# Sheet1.net
KiCad netlist of a schematic drawn in Altium Designer
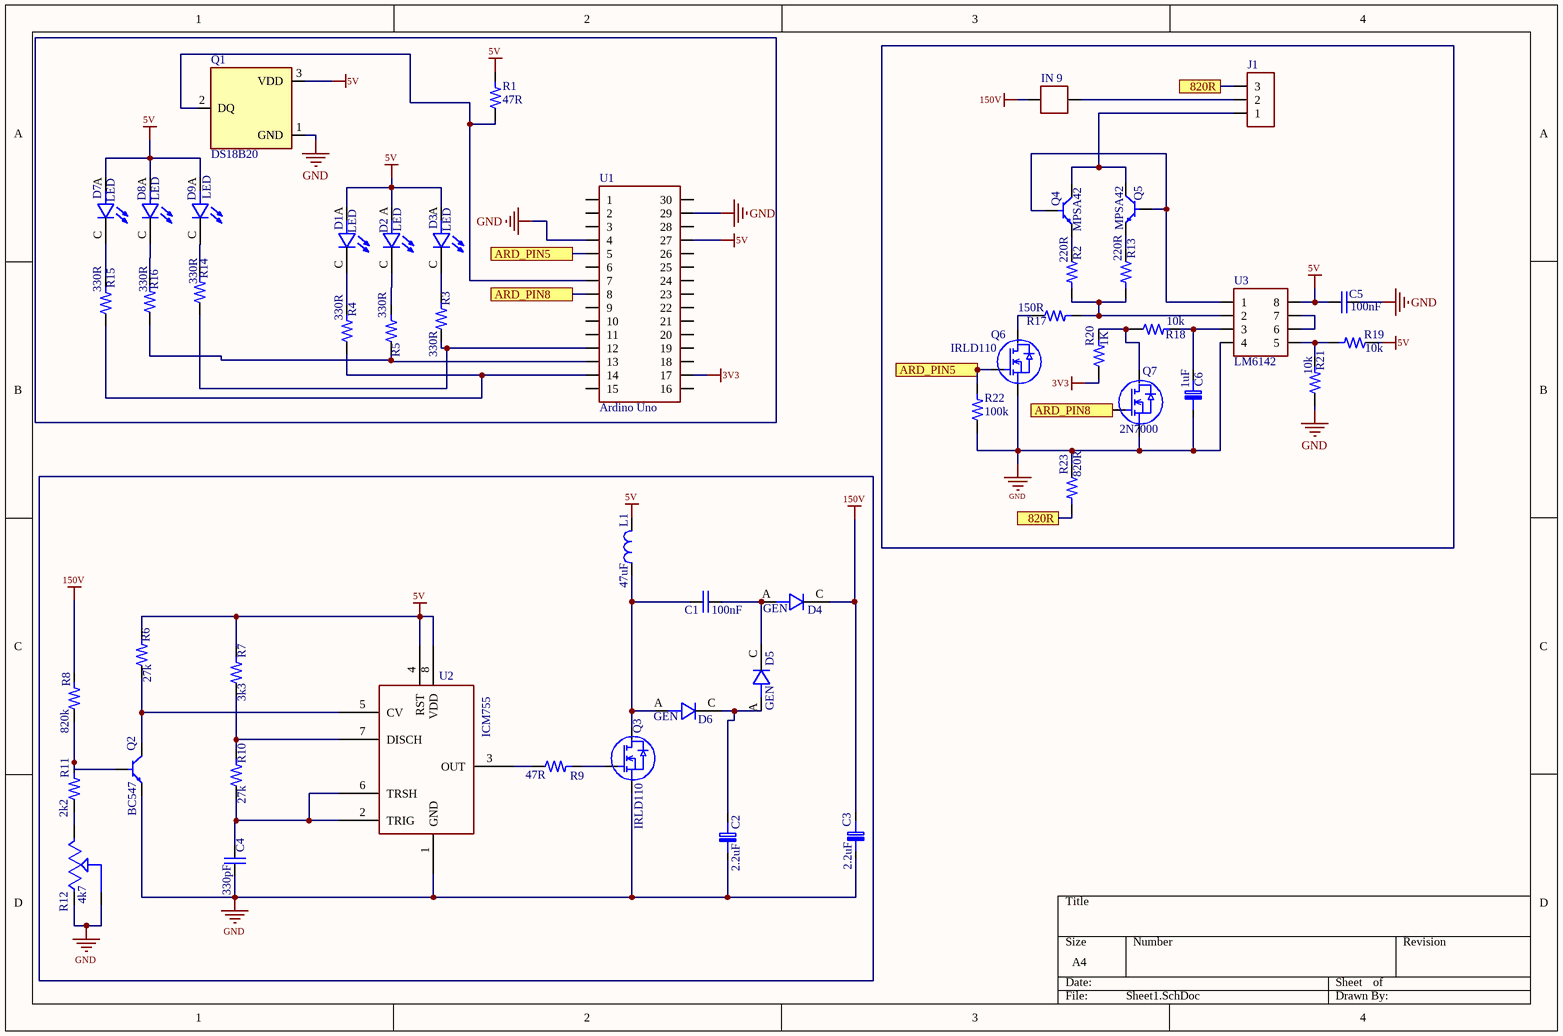
[diagram p0: Sheet1.SchDoc]

(export (version "E")
  (design (tool "Eeschema 10.0.6"))
  (components
    (comp (ref "C1") (value "100nF") (footprint "CAP 0805") (libsource (lib "Schlib1") (part "CAP 100nF")))
    (comp (ref "C2") (value "2.2uF") (footprint "CAP 1005") (libsource (lib "Schlib1") (part "CAP 2.2uF")))
    (comp (ref "C3") (value "2.2uF") (footprint "CAP 1005") (libsource (lib "Schlib1") (part "CAP 2.2uF")))
    (comp (ref "C4") (value "330pF") (footprint "CAP 0805") (libsource (lib "Schlib1") (part "CAP 330pF")))
    (comp (ref "C5") (value "100nF") (footprint "CAP 0805") (libsource (lib "Schlib1") (part "CAP 100nF")))
    (comp (ref "C6") (value "1uF") (footprint "CAP 1005") (libsource (lib "Schlib1") (part "CAP 1uF")))
    (comp (ref "D1") (value "LED") (footprint "LED") (libsource (lib "Schlib1") (part "LED")))
    (comp (ref "D2") (value "LED") (footprint "LED") (libsource (lib "Schlib1") (part "LED")))
    (comp (ref "D3") (value "LED") (footprint "LED") (libsource (lib "Schlib1") (part "LED")))
    (comp (ref "D4") (value "GEN") (footprint "MUR160G") (libsource (lib "Schlib1") (part "Diode")))
    (comp (ref "D5") (value "GEN") (footprint "MUR160G") (libsource (lib "Schlib1") (part "Diode")))
    (comp (ref "D6") (value "GEN") (footprint "MUR160G") (libsource (lib "Schlib1") (part "Diode")))
    (comp (ref "D7") (value "LED") (footprint "LED") (libsource (lib "Schlib1") (part "LED")))
    (comp (ref "D8") (value "LED") (footprint "LED") (libsource (lib "Schlib1") (part "LED")))
    (comp (ref "D9") (value "LED") (footprint "LED") (libsource (lib "Schlib1") (part "LED")))
    (comp (ref "IN 9")
      (value "IN_9 CONNECTOR")
      (footprint "IN 9")
      (libsource (lib "Schlib1") (part "IN_9 CONNECTOR"))
    )
    (comp (ref "J1")
      (value "3 PIN CONNECTOR")
      (footprint "3 PIN CONNECTOR")
      (libsource (lib "Schlib1") (part "3 PIN CONNECTOR"))
    )
    (comp (ref "L1")
      (value "47uF")
      (footprint "INDUCTOR 47uH")
      (libsource (lib "Schlib1") (part "INDUCTOR 47uH"))
    )
    (comp (ref "Q1") (value "DS18B20") (footprint "DS18B20") (libsource (lib "Schlib1") (part "DS18B20")))
    (comp (ref "Q2") (value "BC547") (footprint "BC547") (libsource (lib "Schlib1") (part "BC547")))
    (comp (ref "Q3") (value "IRLD110") (footprint "IRLD110") (libsource (lib "Schlib1") (part "IRLD110")))
    (comp (ref "Q4") (value "MPSA42") (footprint "MPSA42") (libsource (lib "Schlib1") (part "MPSA42")))
    (comp (ref "Q5") (value "MPSA42") (footprint "MPSA42") (libsource (lib "Schlib1") (part "MPSA42")))
    (comp (ref "Q6") (value "IRLD110") (footprint "IRLD110") (libsource (lib "Schlib1") (part "IRLD110")))
    (comp (ref "Q7") (value "2N7000") (footprint "2N7000") (libsource (lib "Schlib1") (part "2N7000")))
    (comp (ref "R1") (value "47R") (footprint "RES 1206") (libsource (lib "Schlib1") (part "RES 47R")))
    (comp (ref "R2") (value "220R") (footprint "RES 1206") (libsource (lib "Schlib1") (part "RES 220R")))
    (comp (ref "R3") (value "330R") (footprint "RES 1206") (libsource (lib "Schlib1") (part "RES 330")))
    (comp (ref "R4") (value "330R") (footprint "RES 1206") (libsource (lib "Schlib1") (part "RES 330")))
    (comp (ref "R5") (value "330R") (footprint "RES 1206") (libsource (lib "Schlib1") (part "RES 330")))
    (comp (ref "R6") (value "27k") (footprint "RES 1206") (libsource (lib "Schlib1") (part "RES 27K")))
    (comp (ref "R7") (value "3k3") (footprint "RES 1206") (libsource (lib "Schlib1") (part "RES 3K3")))
    (comp (ref "R8") (value "820k") (footprint "RES 1206") (libsource (lib "Schlib1") (part "RES 820K")))
    (comp (ref "R9") (value "47R") (footprint "RES 1206") (libsource (lib "Schlib1") (part "RES 47R")))
    (comp (ref "R10") (value "27k") (footprint "RES 1206") (libsource (lib "Schlib1") (part "RES 27K")))
    (comp (ref "R11") (value "2k2") (footprint "RES 1206") (libsource (lib "Schlib1") (part "RES 2K2")))
    (comp (ref "R12")
      (value "4k7")
      (footprint "POTENTIOMETER")
      (libsource (lib "Schlib1") (part "POTENTIOMETER"))
    )
    (comp (ref "R13") (value "220R") (footprint "RES 1206") (libsource (lib "Schlib1") (part "RES 220R")))
    (comp (ref "R14") (value "330R") (footprint "RES 1206") (libsource (lib "Schlib1") (part "RES 330")))
    (comp (ref "R15") (value "330R") (footprint "RES 1206") (libsource (lib "Schlib1") (part "RES 330")))
    (comp (ref "R16") (value "330R") (footprint "RES 1206") (libsource (lib "Schlib1") (part "RES 330")))
    (comp (ref "R17") (value "150R") (footprint "RES 1206") (libsource (lib "Schlib1") (part "RES 150R")))
    (comp (ref "R18") (value "10k") (footprint "RES 1206") (libsource (lib "Schlib1") (part "RES 10K")))
    (comp (ref "R19") (value "10k") (footprint "RES 1206") (libsource (lib "Schlib1") (part "RES 10K")))
    (comp (ref "R20") (value "1K") (footprint "RES 1206") (libsource (lib "Schlib1") (part "RES 1K")))
    (comp (ref "R21") (value "10k") (footprint "RES 1206") (libsource (lib "Schlib1") (part "RES 10K")))
    (comp (ref "R22") (value "100k") (footprint "RES 1206") (libsource (lib "Schlib1") (part "RES 100K")))
    (comp (ref "R23") (value "820R") (footprint "RES 1206") (libsource (lib "Schlib1") (part "RES 820R")))
    (comp (ref "U1")
      (value "Ardino Uno")
      (footprint "ARDUINO NANO")
      (libsource (lib "Schlib1") (part "ARDUINO NANO"))
    )
    (comp (ref "U2") (value "ICM755") (footprint "ICM7555") (libsource (lib "Schlib1") (part "ICM755")))
    (comp (ref "U3") (value "LM6142") (footprint "LM6142") (libsource (lib "Schlib1") (part "LM6142")))
  )
  (nets
    (net (code "1") (name "/820R") (class "Default")
      (node (ref "J1") (pin "3") (pinfunction "3_3") (pintype "passive"))
      (node (ref "R23") (pin "2") (pinfunction "2_2") (pintype "passive"))
    )
    (net (code "2") (name "/ARD_PIN5") (class "Default")
      (node (ref "Q6") (pin "G") (pinfunction "G_G") (pintype "passive"))
      (node (ref "R22") (pin "2") (pinfunction "2_2") (pintype "passive"))
      (node (ref "U1") (pin "5") (pinfunction "5_5") (pintype "passive"))
    )
    (net (code "3") (name "/ARD_PIN8") (class "Default")
      (node (ref "Q7") (pin "1") (pinfunction "1_1") (pintype "passive"))
      (node (ref "U1") (pin "8") (pinfunction "8_8") (pintype "passive"))
    )
    (net (code "4") (name "3V3") (class "Default")
      (node (ref "R20") (pin "1") (pinfunction "1_1") (pintype "passive"))
      (node (ref "U1") (pin "17") (pinfunction "17_17") (pintype "passive"))
    )
    (net (code "5") (name "5V") (class "Default")
      (node (ref "C5") (pin "1") (pinfunction "1_1") (pintype "passive"))
      (node (ref "D1") (pin "A") (pinfunction "A_A") (pintype "passive"))
      (node (ref "D2") (pin "A") (pinfunction "A_A") (pintype "passive"))
      (node (ref "D3") (pin "A") (pinfunction "A_A") (pintype "passive"))
      (node (ref "D7") (pin "A") (pinfunction "A_A") (pintype "passive"))
      (node (ref "D8") (pin "A") (pinfunction "A_A") (pintype "passive"))
      (node (ref "D9") (pin "A") (pinfunction "A_A") (pintype "passive"))
      (node (ref "L1") (pin "2") (pinfunction "2_2") (pintype "passive"))
      (node (ref "Q1") (pin "3") (pinfunction "VDD_3") (pintype "power_in"))
      (node (ref "R1") (pin "2") (pinfunction "2_2") (pintype "passive"))
      (node (ref "R19") (pin "1") (pinfunction "1_1") (pintype "passive"))
      (node (ref "R6") (pin "2") (pinfunction "2_2") (pintype "passive"))
      (node (ref "R7") (pin "2") (pinfunction "2_2") (pintype "passive"))
      (node (ref "U1") (pin "27") (pinfunction "27_27") (pintype "passive"))
      (node (ref "U2") (pin "4") (pinfunction "RST_4") (pintype "passive"))
      (node (ref "U2") (pin "8") (pinfunction "VDD_8") (pintype "passive"))
      (node (ref "U3") (pin "8") (pinfunction "8_8") (pintype "passive"))
    )
    (net (code "6") (name "150V") (class "Default")
      (node (ref "C3") (pin "1") (pinfunction "1_1") (pintype "passive"))
      (node (ref "D4") (pin "C") (pinfunction "C_C") (pintype "passive"))
      (node (ref "IN 9") (pin "1") (pinfunction "1_1") (pintype "passive"))
      (node (ref "R8") (pin "2") (pinfunction "2_2") (pintype "passive"))
    )
    (net (code "7") (name "GND") (class "Default")
      (node (ref "C2") (pin "2") (pinfunction "2_2") (pintype "passive"))
      (node (ref "C3") (pin "2") (pinfunction "2_2") (pintype "passive"))
      (node (ref "C4") (pin "1") (pinfunction "1_1") (pintype "passive"))
      (node (ref "C5") (pin "2") (pinfunction "2_2") (pintype "passive"))
      (node (ref "C6") (pin "2") (pinfunction "2_2") (pintype "passive"))
      (node (ref "Q1") (pin "1") (pinfunction "GND_1") (pintype "power_in"))
      (node (ref "Q2") (pin "3") (pinfunction "3_3") (pintype "passive"))
      (node (ref "Q3") (pin "S") (pinfunction "S_S") (pintype "passive"))
      (node (ref "Q6") (pin "S") (pinfunction "S_S") (pintype "passive"))
      (node (ref "Q7") (pin "2") (pinfunction "2_2") (pintype "passive"))
      (node (ref "R12") (pin "1") (pinfunction "1_1") (pintype "passive"))
      (node (ref "R12") (pin "2") (pinfunction "2_2") (pintype "passive"))
      (node (ref "R21") (pin "1") (pinfunction "1_1") (pintype "passive"))
      (node (ref "R22") (pin "1") (pinfunction "1_1") (pintype "passive"))
      (node (ref "R23") (pin "1") (pinfunction "1_1") (pintype "passive"))
      (node (ref "U1") (pin "29") (pinfunction "29_29") (pintype "passive"))
      (node (ref "U1") (pin "4") (pinfunction "4_4") (pintype "passive"))
      (node (ref "U2") (pin "1") (pinfunction "GND_1") (pintype "passive"))
      (node (ref "U3") (pin "4") (pinfunction "4_4") (pintype "passive"))
    )
    (net (code "8") (name "Net-(C1-Pad1)") (class "Default")
      (node (ref "C1") (pin "1") (pinfunction "1_1") (pintype "passive"))
      (node (ref "D6") (pin "A") (pinfunction "A_A") (pintype "passive"))
      (node (ref "L1") (pin "1") (pinfunction "1_1") (pintype "passive"))
      (node (ref "Q3") (pin "D") (pinfunction "D_D") (pintype "passive"))
    )
    (net (code "9") (name "Net-(C1-Pad2)") (class "Default")
      (node (ref "C1") (pin "2") (pinfunction "2_2") (pintype "passive"))
      (node (ref "D4") (pin "A") (pinfunction "A_A") (pintype "passive"))
      (node (ref "D5") (pin "C") (pinfunction "C_C") (pintype "passive"))
    )
    (net (code "10") (name "Net-(C2-Pad1)") (class "Default")
      (node (ref "C2") (pin "1") (pinfunction "1_1") (pintype "passive"))
      (node (ref "D5") (pin "A") (pinfunction "A_A") (pintype "passive"))
      (node (ref "D6") (pin "C") (pinfunction "C_C") (pintype "passive"))
    )
    (net (code "11") (name "Net-(C6-Pad1)") (class "Default")
      (node (ref "C6") (pin "1") (pinfunction "1_1") (pintype "passive"))
      (node (ref "R18") (pin "2") (pinfunction "2_2") (pintype "passive"))
      (node (ref "U3") (pin "3") (pinfunction "3_3") (pintype "passive"))
    )
    (net (code "12") (name "Net-(D1-PadC)") (class "Default")
      (node (ref "D1") (pin "C") (pinfunction "C_C") (pintype "passive"))
      (node (ref "R4") (pin "2") (pinfunction "2_2") (pintype "passive"))
    )
    (net (code "13") (name "Net-(D2-PadC)") (class "Default")
      (node (ref "D2") (pin "C") (pinfunction "C_C") (pintype "passive"))
      (node (ref "R5") (pin "2") (pinfunction "2_2") (pintype "passive"))
    )
    (net (code "14") (name "Net-(D3-PadC)") (class "Default")
      (node (ref "D3") (pin "C") (pinfunction "C_C") (pintype "passive"))
      (node (ref "R3") (pin "2") (pinfunction "2_2") (pintype "passive"))
    )
    (net (code "15") (name "Net-(D7-PadC)") (class "Default")
      (node (ref "D7") (pin "C") (pinfunction "C_C") (pintype "passive"))
      (node (ref "R15") (pin "2") (pinfunction "2_2") (pintype "passive"))
    )
    (net (code "16") (name "Net-(D8-PadC)") (class "Default")
      (node (ref "D8") (pin "C") (pinfunction "C_C") (pintype "passive"))
      (node (ref "R16") (pin "2") (pinfunction "2_2") (pintype "passive"))
    )
    (net (code "17") (name "Net-(D9-PadC)") (class "Default")
      (node (ref "D9") (pin "C") (pinfunction "C_C") (pintype "passive"))
      (node (ref "R14") (pin "2") (pinfunction "2_2") (pintype "passive"))
    )
    (net (code "18") (name "Net-(IN 9-Pad2)") (class "Default")
      (node (ref "IN 9") (pin "2") (pinfunction "2_2") (pintype "passive"))
      (node (ref "J1") (pin "2") (pinfunction "2_2") (pintype "passive"))
    )
    (net (code "19") (name "Net-(J1-Pad1)") (class "Default")
      (node (ref "J1") (pin "1") (pinfunction "1_1") (pintype "passive"))
      (node (ref "Q4") (pin "3") (pinfunction "3_3") (pintype "passive"))
      (node (ref "Q5") (pin "3") (pinfunction "3_3") (pintype "passive"))
    )
    (net (code "20") (name "Net-(Q1-DQ)") (class "Default")
      (node (ref "Q1") (pin "2") (pinfunction "DQ_2") (pintype "bidirectional"))
      (node (ref "R1") (pin "1") (pinfunction "1_1") (pintype "passive"))
      (node (ref "U1") (pin "7") (pinfunction "7_7") (pintype "passive"))
    )
    (net (code "21") (name "Net-(Q2-Pad2)") (class "Default")
      (node (ref "Q2") (pin "2") (pinfunction "2_2") (pintype "passive"))
      (node (ref "R11") (pin "2") (pinfunction "2_2") (pintype "passive"))
      (node (ref "R8") (pin "1") (pinfunction "1_1") (pintype "passive"))
    )
    (net (code "22") (name "Net-(Q3-PadG)") (class "Default")
      (node (ref "Q3") (pin "G") (pinfunction "G_G") (pintype "passive"))
      (node (ref "R9") (pin "2") (pinfunction "2_2") (pintype "passive"))
    )
    (net (code "23") (name "Net-(Q4-Pad1)") (class "Default")
      (node (ref "Q4") (pin "1") (pinfunction "1_1") (pintype "passive"))
      (node (ref "R2") (pin "1") (pinfunction "1_1") (pintype "passive"))
    )
    (net (code "24") (name "Net-(Q4-Pad2)") (class "Default")
      (node (ref "Q4") (pin "2") (pinfunction "2_2") (pintype "passive"))
      (node (ref "Q5") (pin "2") (pinfunction "2_2") (pintype "passive"))
      (node (ref "U3") (pin "1") (pinfunction "1_1") (pintype "passive"))
    )
    (net (code "25") (name "Net-(Q5-Pad1)") (class "Default")
      (node (ref "Q5") (pin "1") (pinfunction "1_1") (pintype "passive"))
      (node (ref "R13") (pin "1") (pinfunction "1_1") (pintype "passive"))
    )
    (net (code "26") (name "Net-(Q6-PadD)") (class "Default")
      (node (ref "Q6") (pin "D") (pinfunction "D_D") (pintype "passive"))
      (node (ref "R17") (pin "1") (pinfunction "1_1") (pintype "passive"))
    )
    (net (code "27") (name "Net-(Q7-Pad3)") (class "Default")
      (node (ref "Q7") (pin "3") (pinfunction "3_3") (pintype "passive"))
      (node (ref "R18") (pin "1") (pinfunction "1_1") (pintype "passive"))
      (node (ref "R20") (pin "2") (pinfunction "2_2") (pintype "passive"))
    )
    (net (code "28") (name "Net-(R11-Pad1)") (class "Default")
      (node (ref "R11") (pin "1") (pinfunction "1_1") (pintype "passive"))
      (node (ref "R12") (pin "3") (pinfunction "3_3") (pintype "passive"))
    )
    (net (code "29") (name "Net-(R13-Pad2)") (class "Default")
      (node (ref "R13") (pin "2") (pinfunction "2_2") (pintype "passive"))
      (node (ref "R17") (pin "2") (pinfunction "2_2") (pintype "passive"))
      (node (ref "R2") (pin "2") (pinfunction "2_2") (pintype "passive"))
      (node (ref "U3") (pin "2") (pinfunction "2_2") (pintype "passive"))
    )
    (net (code "30") (name "Net-(R14-Pad1)") (class "Default")
      (node (ref "R14") (pin "1") (pinfunction "1_1") (pintype "passive"))
      (node (ref "R3") (pin "1") (pinfunction "1_1") (pintype "passive"))
      (node (ref "U1") (pin "12") (pinfunction "12_12") (pintype "passive"))
    )
    (net (code "31") (name "Net-(R15-Pad1)") (class "Default")
      (node (ref "R15") (pin "1") (pinfunction "1_1") (pintype "passive"))
      (node (ref "R4") (pin "1") (pinfunction "1_1") (pintype "passive"))
      (node (ref "U1") (pin "14") (pinfunction "14_14") (pintype "passive"))
    )
    (net (code "32") (name "Net-(R16-Pad1)") (class "Default")
      (node (ref "R16") (pin "1") (pinfunction "1_1") (pintype "passive"))
      (node (ref "R5") (pin "1") (pinfunction "1_1") (pintype "passive"))
      (node (ref "U1") (pin "13") (pinfunction "13_13") (pintype "passive"))
    )
    (net (code "33") (name "Net-(R19-Pad2)") (class "Default")
      (node (ref "R19") (pin "2") (pinfunction "2_2") (pintype "passive"))
      (node (ref "R21") (pin "2") (pinfunction "2_2") (pintype "passive"))
      (node (ref "U3") (pin "5") (pinfunction "5_5") (pintype "passive"))
    )
    (net (code "34") (name "Net-(U2-CV)") (class "Default")
      (node (ref "Q2") (pin "1") (pinfunction "1_1") (pintype "passive"))
      (node (ref "R6") (pin "1") (pinfunction "1_1") (pintype "passive"))
      (node (ref "U2") (pin "5") (pinfunction "CV_5") (pintype "passive"))
    )
    (net (code "35") (name "Net-(U2-DISCH)") (class "Default")
      (node (ref "R10") (pin "2") (pinfunction "2_2") (pintype "passive"))
      (node (ref "R7") (pin "1") (pinfunction "1_1") (pintype "passive"))
      (node (ref "U2") (pin "7") (pinfunction "DISCH_7") (pintype "passive"))
    )
    (net (code "36") (name "Net-(U2-OUT)") (class "Default")
      (node (ref "R9") (pin "1") (pinfunction "1_1") (pintype "passive"))
      (node (ref "U2") (pin "3") (pinfunction "OUT_3") (pintype "passive"))
    )
    (net (code "37") (name "Net-(U2-TRIG)") (class "Default")
      (node (ref "C4") (pin "2") (pinfunction "2_2") (pintype "passive"))
      (node (ref "R10") (pin "1") (pinfunction "1_1") (pintype "passive"))
      (node (ref "U2") (pin "2") (pinfunction "TRIG_2") (pintype "passive"))
      (node (ref "U2") (pin "6") (pinfunction "TRSH_6") (pintype "passive"))
    )
    (net (code "38") (name "Net-(U3-Pad6)") (class "Default")
      (node (ref "U3") (pin "6") (pinfunction "6_6") (pintype "passive"))
      (node (ref "U3") (pin "7") (pinfunction "7_7") (pintype "passive"))
    )
    (net (code "39") (name "unconnected-(U1-Pad1)") (class "Default")
      (node (ref "U1") (pin "1") (pinfunction "1_1") (pintype "passive"))
    )
    (net (code "40") (name "unconnected-(U1-Pad2)") (class "Default")
      (node (ref "U1") (pin "2") (pinfunction "2_2") (pintype "passive"))
    )
    (net (code "41") (name "unconnected-(U1-Pad3)") (class "Default")
      (node (ref "U1") (pin "3") (pinfunction "3_3") (pintype "passive"))
    )
    (net (code "42") (name "unconnected-(U1-Pad6)") (class "Default")
      (node (ref "U1") (pin "6") (pinfunction "6_6") (pintype "passive"))
    )
    (net (code "43") (name "unconnected-(U1-Pad9)") (class "Default")
      (node (ref "U1") (pin "9") (pinfunction "9_9") (pintype "passive"))
    )
    (net (code "44") (name "unconnected-(U1-Pad10)") (class "Default")
      (node (ref "U1") (pin "10") (pinfunction "10_10") (pintype "passive"))
    )
    (net (code "45") (name "unconnected-(U1-Pad11)") (class "Default")
      (node (ref "U1") (pin "11") (pinfunction "11_11") (pintype "passive"))
    )
    (net (code "46") (name "unconnected-(U1-Pad15)") (class "Default")
      (node (ref "U1") (pin "15") (pinfunction "15_15") (pintype "passive"))
    )
    (net (code "47") (name "unconnected-(U1-Pad16)") (class "Default")
      (node (ref "U1") (pin "16") (pinfunction "16_16") (pintype "passive"))
    )
    (net (code "48") (name "unconnected-(U1-Pad18)") (class "Default")
      (node (ref "U1") (pin "18") (pinfunction "18_18") (pintype "passive"))
    )
    (net (code "49") (name "unconnected-(U1-Pad19)") (class "Default")
      (node (ref "U1") (pin "19") (pinfunction "19_19") (pintype "passive"))
    )
    (net (code "50") (name "unconnected-(U1-Pad20)") (class "Default")
      (node (ref "U1") (pin "20") (pinfunction "20_20") (pintype "passive"))
    )
    (net (code "51") (name "unconnected-(U1-Pad21)") (class "Default")
      (node (ref "U1") (pin "21") (pinfunction "21_21") (pintype "passive"))
    )
    (net (code "52") (name "unconnected-(U1-Pad22)") (class "Default")
      (node (ref "U1") (pin "22") (pinfunction "22_22") (pintype "passive"))
    )
    (net (code "53") (name "unconnected-(U1-Pad23)") (class "Default")
      (node (ref "U1") (pin "23") (pinfunction "23_23") (pintype "passive"))
    )
    (net (code "54") (name "unconnected-(U1-Pad24)") (class "Default")
      (node (ref "U1") (pin "24") (pinfunction "24_24") (pintype "passive"))
    )
    (net (code "55") (name "unconnected-(U1-Pad25)") (class "Default")
      (node (ref "U1") (pin "25") (pinfunction "25_25") (pintype "passive"))
    )
    (net (code "56") (name "unconnected-(U1-Pad26)") (class "Default")
      (node (ref "U1") (pin "26") (pinfunction "26_26") (pintype "passive"))
    )
    (net (code "57") (name "unconnected-(U1-Pad28)") (class "Default")
      (node (ref "U1") (pin "28") (pinfunction "28_28") (pintype "passive"))
    )
    (net (code "58") (name "unconnected-(U1-Pad30)") (class "Default")
      (node (ref "U1") (pin "30") (pinfunction "30_30") (pintype "passive"))
    )
  )
)
